# Weight_Module.net
KiCad netlist of a schematic drawn in Altium Designer
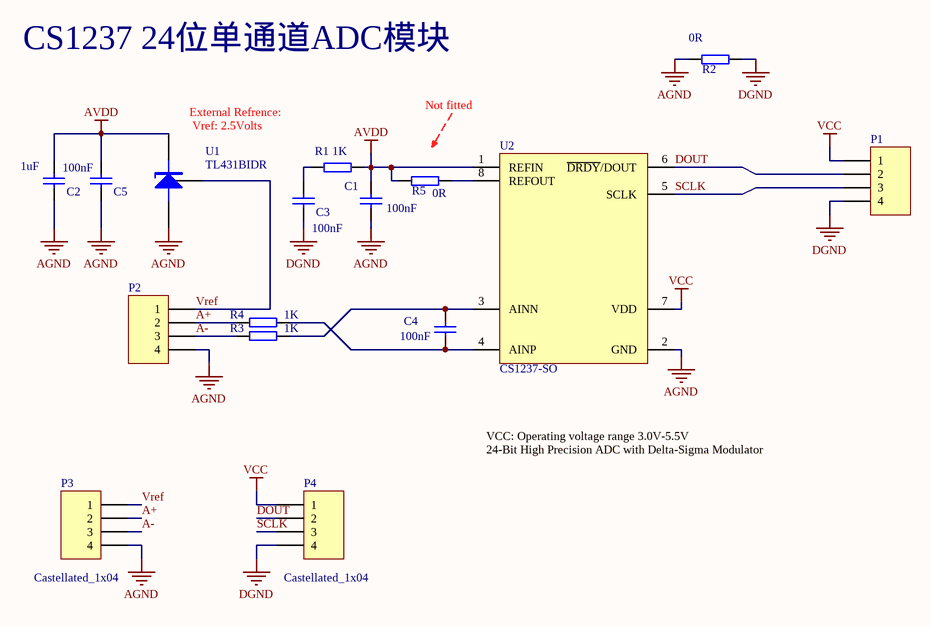
[diagram p0: Weight_Module.SchDoc]

(export (version "E")
  (design (tool "Eeschema 10.0.6"))
  (components
    (comp (ref "C1")
      (value "100nF")
      (footprint "C0603")
      (description "Capacitor, X5R, ±10%, 6.3V")
      (fields
        (field (name "PART NUMBER") "C0603-N.C.")
        (field (name "MANUFACTURER") "N.A.")
        (field (name "PUBLISHER") "Nordic Semiconductor")
      )
      (libsource (lib "adafruit") (part "Cap_0603"))
    )
    (comp (ref "C2")
      (value "1uF")
      (footprint "C0603")
      (description "Capacitor, X5R, ±10%, 6.3V")
      (fields
        (field (name "PART NUMBER") "C0603-N.C.")
        (field (name "MANUFACTURER") "N.A.")
        (field (name "PUBLISHER") "Nordic Semiconductor")
      )
      (libsource (lib "adafruit") (part "Cap_0603"))
    )
    (comp (ref "C3")
      (value "100nF")
      (footprint "C0603")
      (description "Capacitor, X5R, ±10%, 6.3V")
      (fields
        (field (name "PART NUMBER") "C0603-N.C.")
        (field (name "MANUFACTURER") "N.A.")
        (field (name "PUBLISHER") "Nordic Semiconductor")
      )
      (libsource (lib "adafruit") (part "Cap_0603"))
    )
    (comp (ref "C4")
      (value "100nF")
      (footprint "C0603")
      (description "Capacitor, X5R, ±10%, 6.3V")
      (fields
        (field (name "PART NUMBER") "C0603-N.C.")
        (field (name "MANUFACTURER") "N.A.")
        (field (name "PUBLISHER") "Nordic Semiconductor")
      )
      (libsource (lib "adafruit") (part "Cap_0603"))
    )
    (comp (ref "C5")
      (value "100nF")
      (footprint "C0603")
      (description "Capacitor, X5R, ±10%, 6.3V")
      (fields
        (field (name "PART NUMBER") "C0603-N.C.")
        (field (name "MANUFACTURER") "N.A.")
        (field (name "PUBLISHER") "Nordic Semiconductor")
      )
      (libsource (lib "adafruit") (part "Cap_0603"))
    )
    (comp (ref "P1")
      (value "~")
      (footprint "HDR1X4")
      (description "Header, 4-Pin")
      (fields (field (name "PUBLISHER") "Altium Limited"))
      (libsource (lib "") (part "Header 4_1"))
    )
    (comp (ref "P2")
      (value "~")
      (footprint "HDR1X4")
      (description "Header, 4-Pin")
      (fields (field (name "PUBLISHER") "Altium Limited"))
      (libsource (lib "Miscellaneous Connectors") (part "Header 4"))
    )
    (comp (ref "P3")
      (value "Castellated_1x04")
      (footprint "Castellated_1X04")
      (description "Header, 4-Pin")
      (fields (field (name "PUBLISHER") "Altium Limited"))
      (libsource (lib "") (part "Castellated_1x04_1"))
    )
    (comp (ref "P4")
      (value "Castellated_1x04")
      (footprint "Castellated_1X04")
      (description "Header, 4-Pin")
      (fields (field (name "PUBLISHER") "Altium Limited"))
      (libsource (lib "adafruit") (part "Castellated_1x04"))
    )
    (comp (ref "R1")
      (value "1kΩ")
      (footprint "R0805")
      (description "Resistor, ±1%, 0.200W")
      (libsource (lib "") (part "Res_0805_1"))
    )
    (comp (ref "R2")
      (value "0Ω")
      (footprint "R0805")
      (description "Resistor, ±1%, 0.200W")
      (libsource (lib "adafruit") (part "Res_0805"))
    )
    (comp (ref "R3")
      (value "1kΩ")
      (footprint "R0603")
      (description "Resistor, ±1%, 0.100W")
      (fields
        (field (name "PART NUMBER") "R0603-N.C.Ω")
        (field (name "MANUFACTURER") "N.A.")
        (field (name "PUBLISHER") "Nordic Semiconductor")
      )
      (libsource (lib "adafruit") (part "Res_0603"))
    )
    (comp (ref "R4")
      (value "1kΩ")
      (footprint "R0603")
      (description "Resistor, ±1%, 0.100W")
      (fields
        (field (name "PART NUMBER") "R0603-N.C.Ω")
        (field (name "MANUFACTURER") "N.A.")
        (field (name "PUBLISHER") "Nordic Semiconductor")
      )
      (libsource (lib "adafruit") (part "Res_0603"))
    )
    (comp (ref "R5")
      (value "0Ω")
      (footprint "R0603")
      (description "Resistor, ±1%, 0.100W")
      (fields
        (field (name "PART NUMBER") "R0603-N.C.Ω")
        (field (name "MANUFACTURER") "N.A.")
        (field (name "PUBLISHER") "Nordic Semiconductor")
      )
      (libsource (lib "adafruit") (part "Res_0603"))
    )
    (comp (ref "U1")
      (value "TL431BIDR")
      (footprint "SOIC-8E")
      (description "TL431, TL432 Precision Programmable Reference")
      (fields (field (name "MANUFACTURER") "TI(德州仪器)") (field (name "TOLERANCE") "±0.5%"))
      (libsource (lib "adafruit") (part "TL431BIDR"))
    )
    (comp (ref "U2")
      (value "CS1237-SO")
      (footprint "SOIC-8E")
      (description "CS1237 24-Bit High Precision ADC with Delta-Sigma Modulator")
      (fields (field (name "MANUFACTURER") "CHIPSEA(芯海科技)") (field (name "CONTRIBUTOR") "lcsc"))
      (libsource (lib "adafruit") (part "CS1237-SO_C7464028"))
    )
  )
  (nets
    (net (code "1") (name "/A+") (class "Default")
      (node (ref "P2") (pin "2") (pinfunction "2_2") (pintype "passive"))
      (node (ref "P3") (pin "2") (pinfunction "2_2") (pintype "passive"))
      (node (ref "R4") (pin "2") (pinfunction "2_2") (pintype "passive"))
    )
    (net (code "2") (name "/A-") (class "Default")
      (node (ref "P2") (pin "3") (pinfunction "3_3") (pintype "passive"))
      (node (ref "P3") (pin "3") (pinfunction "3_3") (pintype "passive"))
      (node (ref "R3") (pin "2") (pinfunction "2_2") (pintype "passive"))
    )
    (net (code "3") (name "/DOUT") (class "Default")
      (node (ref "P1") (pin "2") (pinfunction "2_2") (pintype "passive"))
      (node (ref "P4") (pin "2") (pinfunction "2_2") (pintype "passive"))
      (node (ref "U2") (pin "6") (pinfunction "~{DRDY}/DOUT_6") (pintype "passive"))
    )
    (net (code "4") (name "/SCLK") (class "Default")
      (node (ref "P1") (pin "3") (pinfunction "3_3") (pintype "passive"))
      (node (ref "P4") (pin "3") (pinfunction "3_3") (pintype "passive"))
      (node (ref "U2") (pin "5") (pinfunction "SCLK_5") (pintype "passive"))
    )
    (net (code "5") (name "/Vref") (class "Default")
      (node (ref "P2") (pin "1") (pinfunction "1_1") (pintype "passive"))
      (node (ref "P3") (pin "1") (pinfunction "1_1") (pintype "passive"))
      (node (ref "U1") (pin "8") (pinfunction "Ref_8") (pintype "passive"))
    )
    (net (code "6") (name "AGND") (class "Default")
      (node (ref "C1") (pin "2") (pinfunction "2_2") (pintype "passive"))
      (node (ref "C2") (pin "1") (pinfunction "1_1") (pintype "passive"))
      (node (ref "C5") (pin "2") (pinfunction "2_2") (pintype "passive"))
      (node (ref "P2") (pin "4") (pinfunction "4_4") (pintype "passive"))
      (node (ref "P3") (pin "4") (pinfunction "4_4") (pintype "passive"))
      (node (ref "R2") (pin "2") (pinfunction "2_2") (pintype "passive"))
      (node (ref "U1") (pin "3") (pinfunction "A_3") (pintype "passive"))
      (node (ref "U2") (pin "2") (pinfunction "GND_2") (pintype "passive"))
    )
    (net (code "7") (name "AVDD") (class "Default")
      (node (ref "C1") (pin "1") (pinfunction "1_1") (pintype "passive"))
      (node (ref "C2") (pin "2") (pinfunction "2_2") (pintype "passive"))
      (node (ref "C5") (pin "1") (pinfunction "1_1") (pintype "passive"))
      (node (ref "R1") (pin "2") (pinfunction "2_2") (pintype "passive"))
      (node (ref "R5") (pin "2") (pinfunction "2_2") (pintype "passive"))
      (node (ref "U1") (pin "1") (pinfunction "K_1") (pintype "passive"))
      (node (ref "U2") (pin "1") (pinfunction "REFIN_1") (pintype "passive"))
    )
    (net (code "8") (name "DGND") (class "Default")
      (node (ref "C3") (pin "2") (pinfunction "2_2") (pintype "passive"))
      (node (ref "P1") (pin "4") (pinfunction "4_4") (pintype "passive"))
      (node (ref "P4") (pin "4") (pinfunction "4_4") (pintype "passive"))
      (node (ref "R2") (pin "1") (pinfunction "1_1") (pintype "passive"))
    )
    (net (code "9") (name "Net-(C3-Pad1)") (class "Default")
      (node (ref "C3") (pin "1") (pinfunction "1_1") (pintype "passive"))
      (node (ref "R1") (pin "1") (pinfunction "1_1") (pintype "passive"))
    )
    (net (code "10") (name "Net-(U2-AINN)") (class "Default")
      (node (ref "C4") (pin "1") (pinfunction "1_1") (pintype "passive"))
      (node (ref "R3") (pin "1") (pinfunction "1_1") (pintype "passive"))
      (node (ref "U2") (pin "3") (pinfunction "AINN_3") (pintype "passive"))
    )
    (net (code "11") (name "Net-(U2-AINP)") (class "Default")
      (node (ref "C4") (pin "2") (pinfunction "2_2") (pintype "passive"))
      (node (ref "R4") (pin "1") (pinfunction "1_1") (pintype "passive"))
      (node (ref "U2") (pin "4") (pinfunction "AINP_4") (pintype "passive"))
    )
    (net (code "12") (name "Net-(U2-REFOUT)") (class "Default")
      (node (ref "R5") (pin "1") (pinfunction "1_1") (pintype "passive"))
      (node (ref "U2") (pin "8") (pinfunction "REFOUT_8") (pintype "passive"))
    )
    (net (code "13") (name "VCC") (class "Default")
      (node (ref "P1") (pin "1") (pinfunction "1_1") (pintype "passive"))
      (node (ref "P4") (pin "1") (pinfunction "1_1") (pintype "passive"))
      (node (ref "U2") (pin "7") (pinfunction "VDD_7") (pintype "passive"))
    )
    (net (code "14") (name "unconnected-(U1-NC-Pad4)") (class "Default")
      (node (ref "U1") (pin "4") (pinfunction "NC_4") (pintype "passive"))
    )
    (net (code "15") (name "unconnected-(U1-NC-Pad5)") (class "Default")
      (node (ref "U1") (pin "5") (pinfunction "NC_5") (pintype "passive"))
    )
  )
)
